# ACME_V4_2.net
KiCad netlist of a schematic drawn in EAGLE
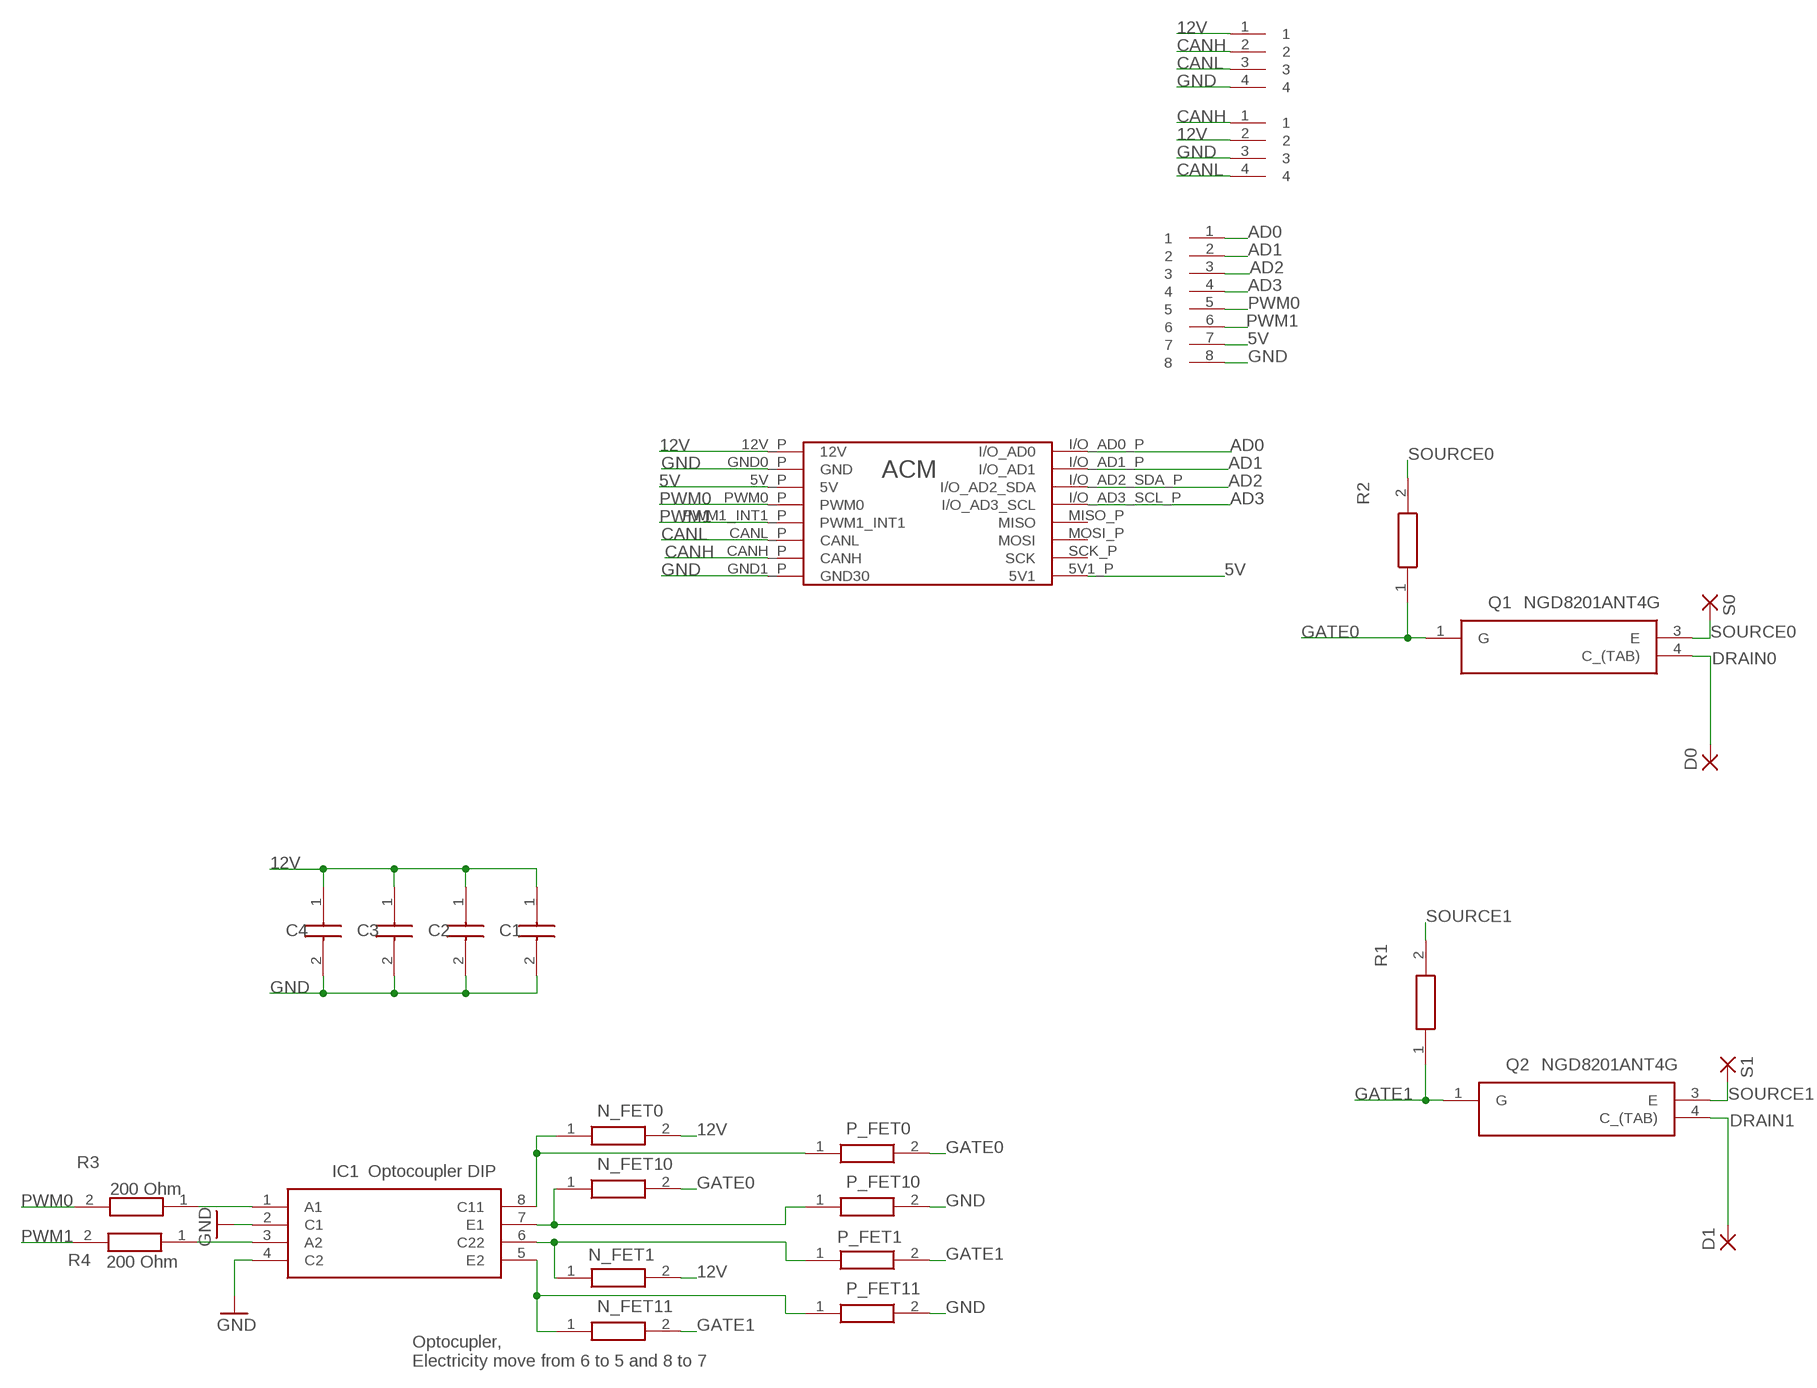
[diagram p0: schematic, sheet 1]

(export (version "E")
  (design (tool "Eeschema 10.0.6"))
  (components
    (comp (ref "C1")
      (value "TACL105K006XTA")
      (footprint "eagle-import:CAPPC1709X100N")
      (fields (field (name "MOUSER_PART_NUMBER") "581-TACL105K006X"))
      (libsource (lib "eagle-import") (part "TACL105K006XTA"))
    )
    (comp (ref "C2")
      (value "TACL105K006XTA")
      (footprint "eagle-import:CAPPC1709X100N")
      (fields (field (name "MOUSER_PART_NUMBER") "581-TACL105K006X"))
      (libsource (lib "eagle-import") (part "TACL105K006XTA"))
    )
    (comp (ref "C3")
      (value "TACL105K006XTA")
      (footprint "eagle-import:CAPPC1709X100N")
      (fields (field (name "MOUSER_PART_NUMBER") "581-TACL105K006X"))
      (libsource (lib "eagle-import") (part "TACL105K006XTA"))
    )
    (comp (ref "C4")
      (value "TACL105K006XTA")
      (footprint "eagle-import:CAPPC1709X100N")
      (fields (field (name "MOUSER_PART_NUMBER") "581-TACL105K006X"))
      (libsource (lib "eagle-import") (part "TACL105K006XTA"))
    )
    (comp (ref "D0")
      (value "WIREPADSMD5-2,5")
      (footprint "eagle-import:5-2,5")
      (libsource (lib "eagle-import") (part "WIREPADSMD5-2,5"))
    )
    (comp (ref "D1")
      (value "WIREPADSMD5-2,5")
      (footprint "eagle-import:5-2,5")
      (libsource (lib "eagle-import") (part "WIREPADSMD5-2,5"))
    )
    (comp (ref "IC1")
      (value "Optocoupler DIP")
      (footprint "eagle-import:DIP762W60P254L966H485Q8N")
      (fields
        (field (name "MANUFACTURER_PART_NUMBER") "TLP350(F)")
        (field (name "MOUSER_PART_NUMBER") "757-TLP350(F)")
        (field (name "RS_PART_NUMBER") "0186022P")
      )
      (libsource (lib "eagle-import") (part "TLP350(F)"))
    )
    (comp (ref "N_FET0")
      (value "ERA-3AEB2262V")
      (footprint "eagle-import:RESC1608X55N")
      (fields (field (name "MOUSER_PART_NUMBER") "667-ERA-3AEB2262V"))
      (libsource (lib "eagle-import") (part "ERA-3AEB2262V"))
    )
    (comp (ref "N_FET1")
      (value "ERA-3AEB2262V")
      (footprint "eagle-import:RESC1608X55N")
      (fields (field (name "MOUSER_PART_NUMBER") "667-ERA-3AEB2262V"))
      (libsource (lib "eagle-import") (part "ERA-3AEB2262V"))
    )
    (comp (ref "N_FET10")
      (value "ERA-3AEB2262V")
      (footprint "eagle-import:RESC1608X55N")
      (fields (field (name "MOUSER_PART_NUMBER") "667-ERA-3AEB2262V"))
      (libsource (lib "eagle-import") (part "ERA-3AEB2262V"))
    )
    (comp (ref "N_FET11")
      (value "ERA-3AEB2262V")
      (footprint "eagle-import:RESC1608X55N")
      (fields (field (name "MOUSER_PART_NUMBER") "667-ERA-3AEB2262V"))
      (libsource (lib "eagle-import") (part "ERA-3AEB2262V"))
    )
    (comp (ref "P_FET0")
      (value "ERA-3AEB2262V")
      (footprint "eagle-import:RESC1608X55N")
      (fields (field (name "MOUSER_PART_NUMBER") "667-ERA-3AEB2262V"))
      (libsource (lib "eagle-import") (part "ERA-3AEB2262V"))
    )
    (comp (ref "P_FET1")
      (value "ERA-3AEB2262V")
      (footprint "eagle-import:RESC1608X55N")
      (fields (field (name "MOUSER_PART_NUMBER") "667-ERA-3AEB2262V"))
      (libsource (lib "eagle-import") (part "ERA-3AEB2262V"))
    )
    (comp (ref "P_FET10")
      (value "ERA-3AEB2262V")
      (footprint "eagle-import:RESC1608X55N")
      (fields (field (name "MOUSER_PART_NUMBER") "667-ERA-3AEB2262V"))
      (libsource (lib "eagle-import") (part "ERA-3AEB2262V"))
    )
    (comp (ref "P_FET11")
      (value "ERA-3AEB2262V")
      (footprint "eagle-import:RESC1608X55N")
      (fields (field (name "MOUSER_PART_NUMBER") "667-ERA-3AEB2262V"))
      (libsource (lib "eagle-import") (part "ERA-3AEB2262V"))
    )
    (comp (ref "Q1")
      (value "NGD8201ANT4G")
      (footprint "eagle-import:TO229P990X238-4N")
      (fields (field (name "MOUSER_PART_NUMBER") "7470901"))
      (libsource (lib "eagle-import") (part "NGD8201ANT4G"))
    )
    (comp (ref "Q2")
      (value "NGD8201ANT4G")
      (footprint "eagle-import:TO229P990X238-4N")
      (fields (field (name "MOUSER_PART_NUMBER") "7470901"))
      (libsource (lib "eagle-import") (part "NGD8201ANT4G"))
    )
    (comp (ref "R1")
      (value "ERA-3AEB2262V")
      (footprint "eagle-import:RESC1608X55N")
      (fields (field (name "MOUSER_PART_NUMBER") "667-ERA-3AEB2262V"))
      (libsource (lib "eagle-import") (part "ERA-3AEB2262V"))
    )
    (comp (ref "R2")
      (value "ERA-3AEB2262V")
      (footprint "eagle-import:RESC1608X55N")
      (fields (field (name "MOUSER_PART_NUMBER") "667-ERA-3AEB2262V"))
      (libsource (lib "eagle-import") (part "ERA-3AEB2262V"))
    )
    (comp (ref "R3")
      (value "200 Ohm")
      (footprint "eagle-import:RESC1608X55N")
      (fields
        (field (name "MANUFACTURER_PART_NUMBER") "ERA-3AEB2262V")
        (field (name "MOUSER_PART_NUMBER") "667-ERA-3AEB2262V")
      )
      (libsource (lib "eagle-import") (part "ERA-3AEB2262V"))
    )
    (comp (ref "R4")
      (value "200 Ohm")
      (footprint "eagle-import:RESC1608X55N")
      (fields
        (field (name "MANUFACTURER_PART_NUMBER") "ERA-3AEB2262V")
        (field (name "MOUSER_PART_NUMBER") "667-ERA-3AEB2262V")
      )
      (libsource (lib "eagle-import") (part "ERA-3AEB2262V"))
    )
    (comp (ref "S0")
      (value "WIREPADSMD5-2,5")
      (footprint "eagle-import:5-2,5")
      (libsource (lib "eagle-import") (part "WIREPADSMD5-2,5"))
    )
    (comp (ref "S1")
      (value "WIREPADSMD5-2,5")
      (footprint "eagle-import:5-2,5")
      (libsource (lib "eagle-import") (part "WIREPADSMD5-2,5"))
    )
    (comp (ref "U$1")
      (value "ACM_CASTELLATED")
      (footprint "eagle-import:ACM_CAS_FP")
      (libsource (lib "eagle-import") (part "ACM_CASTELLATED"))
    )
    (comp (ref "U$3")
      (value "16P_CONNECTOR")
      (footprint "eagle-import:16P_CONNECTOR_FP")
      (libsource (lib "eagle-import") (part "16P_CONNECTOR"))
    )
    (comp (ref "U$4")
      (value "16P_CONNECTOR")
      (footprint "eagle-import:16P_CONNECTOR_FP")
      (libsource (lib "eagle-import") (part "16P_CONNECTOR"))
    )
    (comp (ref "U$5")
      (value "16P_CONNECTOR")
      (footprint "eagle-import:16P_CONNECTOR_FP")
      (libsource (lib "eagle-import") (part "8P_Connector holes_Screwterminal_16P_CONNECTOR"))
    )
  )
  (nets
    (net (code "1") (name "/5V") (class "Default")
      (node (ref "U$1") (pin "5V1_P") (pinfunction "5V1_5V1_P") (pintype "bidirectional"))
      (node (ref "U$1") (pin "5V_P") (pinfunction "5V_5V_P") (pintype "bidirectional"))
      (node (ref "U$5") (pin "7") (pinfunction "7_7") (pintype "bidirectional"))
    )
    (net (code "2") (name "/12V") (class "Default")
      (node (ref "C1") (pin "1") (pinfunction "+_1") (pintype "bidirectional"))
      (node (ref "C2") (pin "1") (pinfunction "+_1") (pintype "bidirectional"))
      (node (ref "C3") (pin "1") (pinfunction "+_1") (pintype "bidirectional"))
      (node (ref "C4") (pin "1") (pinfunction "+_1") (pintype "bidirectional"))
      (node (ref "N_FET0") (pin "2") (pinfunction "2_2") (pintype "bidirectional"))
      (node (ref "N_FET1") (pin "2") (pinfunction "2_2") (pintype "bidirectional"))
      (node (ref "U$1") (pin "12V_P") (pinfunction "12V_12V_P") (pintype "bidirectional"))
      (node (ref "U$3") (pin "1") (pinfunction "1_1") (pintype "bidirectional"))
      (node (ref "U$4") (pin "2") (pinfunction "2_2") (pintype "bidirectional"))
    )
    (net (code "3") (name "/AD0") (class "Default")
      (node (ref "U$1") (pin "I/O_AD0_P") (pinfunction "I/O_AD0_I/O_AD0_P") (pintype "bidirectional"))
      (node (ref "U$5") (pin "1") (pinfunction "1_1") (pintype "bidirectional"))
    )
    (net (code "4") (name "/AD1") (class "Default")
      (node (ref "U$1") (pin "I/O_AD1_P") (pinfunction "I/O_AD1_I/O_AD1_P") (pintype "bidirectional"))
      (node (ref "U$5") (pin "2") (pinfunction "2_2") (pintype "bidirectional"))
    )
    (net (code "5") (name "/AD2") (class "Default")
      (node (ref "U$1") (pin "I/O_AD2_SDA_P") (pinfunction "I/O_AD2_SDA_I/O_AD2_SDA_P") (pintype "bidirectional"))
      (node (ref "U$5") (pin "3") (pinfunction "3_3") (pintype "bidirectional"))
    )
    (net (code "6") (name "/AD3") (class "Default")
      (node (ref "U$1") (pin "I/O_AD3_SCL_P") (pinfunction "I/O_AD3_SCL_I/O_AD3_SCL_P") (pintype "bidirectional"))
      (node (ref "U$5") (pin "4") (pinfunction "4_4") (pintype "bidirectional"))
    )
    (net (code "7") (name "/CANH") (class "Default")
      (node (ref "U$1") (pin "CANH_P") (pinfunction "CANH_CANH_P") (pintype "bidirectional"))
      (node (ref "U$3") (pin "2") (pinfunction "2_2") (pintype "bidirectional"))
      (node (ref "U$4") (pin "1") (pinfunction "1_1") (pintype "bidirectional"))
    )
    (net (code "8") (name "/CANL") (class "Default")
      (node (ref "U$1") (pin "CANL_P") (pinfunction "CANL_CANL_P") (pintype "bidirectional"))
      (node (ref "U$3") (pin "3") (pinfunction "3_3") (pintype "bidirectional"))
      (node (ref "U$4") (pin "4") (pinfunction "4_4") (pintype "bidirectional"))
    )
    (net (code "9") (name "/DRAIN0") (class "Default")
      (node (ref "D0") (pin "1") (pinfunction "P_1") (pintype "passive"))
      (node (ref "Q1") (pin "4") (pinfunction "C_(TAB)_4") (pintype "bidirectional"))
    )
    (net (code "10") (name "/DRAIN1") (class "Default")
      (node (ref "D1") (pin "1") (pinfunction "P_1") (pintype "passive"))
      (node (ref "Q2") (pin "4") (pinfunction "C_(TAB)_4") (pintype "bidirectional"))
    )
    (net (code "11") (name "/GATE0") (class "Default")
      (node (ref "N_FET10") (pin "2") (pinfunction "2_2") (pintype "bidirectional"))
      (node (ref "P_FET0") (pin "2") (pinfunction "2_2") (pintype "bidirectional"))
      (node (ref "Q1") (pin "1") (pinfunction "G_1") (pintype "bidirectional"))
      (node (ref "R2") (pin "1") (pinfunction "1_1") (pintype "bidirectional"))
    )
    (net (code "12") (name "/GATE1") (class "Default")
      (node (ref "N_FET11") (pin "2") (pinfunction "2_2") (pintype "bidirectional"))
      (node (ref "P_FET1") (pin "2") (pinfunction "2_2") (pintype "bidirectional"))
      (node (ref "Q2") (pin "1") (pinfunction "G_1") (pintype "bidirectional"))
      (node (ref "R1") (pin "1") (pinfunction "1_1") (pintype "bidirectional"))
    )
    (net (code "13") (name "/PWM0") (class "Default")
      (node (ref "R3") (pin "2") (pinfunction "2_2") (pintype "bidirectional"))
      (node (ref "U$1") (pin "PWM0_P") (pinfunction "PWM0_PWM0_P") (pintype "bidirectional"))
      (node (ref "U$5") (pin "5") (pinfunction "5_5") (pintype "bidirectional"))
    )
    (net (code "14") (name "/PWM1") (class "Default")
      (node (ref "R4") (pin "2") (pinfunction "2_2") (pintype "bidirectional"))
      (node (ref "U$1") (pin "PWM1_INT1_P") (pinfunction "PWM1_INT1_PWM1_INT1_P") (pintype "bidirectional"))
      (node (ref "U$5") (pin "6") (pinfunction "6_6") (pintype "bidirectional"))
    )
    (net (code "15") (name "/SOURCE0") (class "Default")
      (node (ref "Q1") (pin "3") (pinfunction "E_3") (pintype "bidirectional"))
      (node (ref "R2") (pin "2") (pinfunction "2_2") (pintype "bidirectional"))
      (node (ref "S0") (pin "1") (pinfunction "P_1") (pintype "passive"))
    )
    (net (code "16") (name "/SOURCE1") (class "Default")
      (node (ref "Q2") (pin "3") (pinfunction "E_3") (pintype "bidirectional"))
      (node (ref "R1") (pin "2") (pinfunction "2_2") (pintype "bidirectional"))
      (node (ref "S1") (pin "1") (pinfunction "P_1") (pintype "passive"))
    )
    (net (code "17") (name "GND") (class "Default")
      (node (ref "C1") (pin "2") (pinfunction "-_2") (pintype "bidirectional"))
      (node (ref "C2") (pin "2") (pinfunction "-_2") (pintype "bidirectional"))
      (node (ref "C3") (pin "2") (pinfunction "-_2") (pintype "bidirectional"))
      (node (ref "C4") (pin "2") (pinfunction "-_2") (pintype "bidirectional"))
      (node (ref "IC1") (pin "2") (pinfunction "C1_2") (pintype "bidirectional"))
      (node (ref "IC1") (pin "4") (pinfunction "C2_4") (pintype "bidirectional"))
      (node (ref "P_FET10") (pin "2") (pinfunction "2_2") (pintype "bidirectional"))
      (node (ref "P_FET11") (pin "2") (pinfunction "2_2") (pintype "bidirectional"))
      (node (ref "U$1") (pin "GND0_P") (pinfunction "GND_GND0_P") (pintype "bidirectional"))
      (node (ref "U$1") (pin "GND1_P") (pinfunction "GND30_GND1_P") (pintype "bidirectional"))
      (node (ref "U$3") (pin "4") (pinfunction "4_4") (pintype "bidirectional"))
      (node (ref "U$4") (pin "3") (pinfunction "3_3") (pintype "bidirectional"))
      (node (ref "U$5") (pin "8") (pinfunction "8_8") (pintype "bidirectional"))
    )
    (net (code "18") (name "Net-(IC1-A1)") (class "Default")
      (node (ref "IC1") (pin "1") (pinfunction "A1_1") (pintype "bidirectional"))
      (node (ref "R3") (pin "1") (pinfunction "1_1") (pintype "bidirectional"))
    )
    (net (code "19") (name "Net-(IC1-A2)") (class "Default")
      (node (ref "IC1") (pin "3") (pinfunction "A2_3") (pintype "bidirectional"))
      (node (ref "R4") (pin "1") (pinfunction "1_1") (pintype "bidirectional"))
    )
    (net (code "20") (name "Net-(IC1-C11)") (class "Default")
      (node (ref "IC1") (pin "8") (pinfunction "C11_8") (pintype "bidirectional"))
      (node (ref "N_FET0") (pin "1") (pinfunction "1_1") (pintype "bidirectional"))
      (node (ref "P_FET0") (pin "1") (pinfunction "1_1") (pintype "bidirectional"))
    )
    (net (code "21") (name "Net-(IC1-C22)") (class "Default")
      (node (ref "IC1") (pin "6") (pinfunction "C22_6") (pintype "bidirectional"))
      (node (ref "N_FET1") (pin "1") (pinfunction "1_1") (pintype "bidirectional"))
      (node (ref "P_FET1") (pin "1") (pinfunction "1_1") (pintype "bidirectional"))
    )
    (net (code "22") (name "Net-(IC1-E1)") (class "Default")
      (node (ref "IC1") (pin "7") (pinfunction "E1_7") (pintype "bidirectional"))
      (node (ref "N_FET10") (pin "1") (pinfunction "1_1") (pintype "bidirectional"))
      (node (ref "P_FET10") (pin "1") (pinfunction "1_1") (pintype "bidirectional"))
    )
    (net (code "23") (name "Net-(IC1-E2)") (class "Default")
      (node (ref "IC1") (pin "5") (pinfunction "E2_5") (pintype "bidirectional"))
      (node (ref "N_FET11") (pin "1") (pinfunction "1_1") (pintype "bidirectional"))
      (node (ref "P_FET11") (pin "1") (pinfunction "1_1") (pintype "bidirectional"))
    )
    (net (code "24") (name "unconnected-(U$1-MISO-PadMISO_P)") (class "Default")
      (node (ref "U$1") (pin "MISO_P") (pinfunction "MISO_MISO_P") (pintype "bidirectional"))
    )
    (net (code "25") (name "unconnected-(U$1-MOSI-PadMOSI_P)") (class "Default")
      (node (ref "U$1") (pin "MOSI_P") (pinfunction "MOSI_MOSI_P") (pintype "bidirectional"))
    )
    (net (code "26") (name "unconnected-(U$1-SCK-PadSCK_P)") (class "Default")
      (node (ref "U$1") (pin "SCK_P") (pinfunction "SCK_SCK_P") (pintype "bidirectional"))
    )
  )
)
